# hbridge_ustx.net
KiCad netlist of a schematic drawn in EAGLE
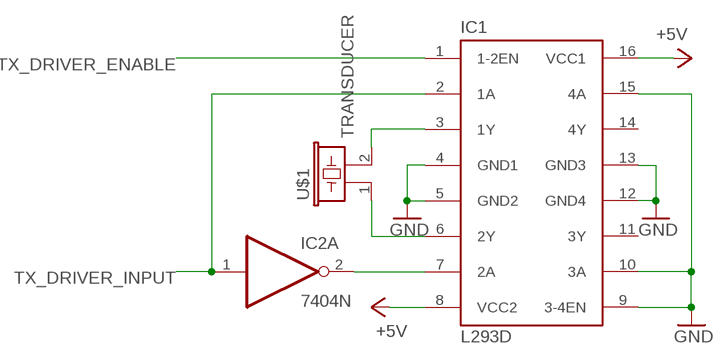
[diagram p0: schematic, sheet 1]

(export (version "E")
  (design (tool "Eeschema 10.0.6"))
  (components
    (comp (ref "IC1")
      (value "L293D")
      (footprint "eagle-import:DIL16")
      (libsource (lib "eagle-import") (part "L293D"))
    )
    (comp (ref "IC2")
      (value "7404N")
      (footprint "eagle-import:DIL14")
      (libsource (lib "eagle-import") (part "7404N"))
    )
    (comp (ref "U$1")
      (value "TRANSDUCER")
      (footprint "eagle-import:TRANSDUCER")
      (libsource (lib "eagle-import") (part "TRANSDUCER"))
    )
  )
  (nets
    (net (code "1") (name "+5V") (class "Default")
      (node (ref "IC1") (pin "16") (pinfunction "VCC1_16") (pintype "power_in"))
      (node (ref "IC1") (pin "8") (pinfunction "VCC2_8") (pintype "power_in"))
    )
    (net (code "2") (name "/TX_DRIVER_ENABLE") (class "Default")
      (node (ref "IC1") (pin "1") (pinfunction "1-2EN_1") (pintype "input"))
    )
    (net (code "3") (name "/TX_DRIVER_INPUT") (class "Default")
      (node (ref "IC1") (pin "2") (pinfunction "1A_2") (pintype "input"))
      (node (ref "IC2") (pin "1") (pinfunction "I_1") (pintype "input"))
    )
    (net (code "4") (name "GND") (class "Default")
      (node (ref "IC1") (pin "10") (pinfunction "3A_10") (pintype "input"))
      (node (ref "IC1") (pin "12") (pinfunction "GND4_12") (pintype "power_in"))
      (node (ref "IC1") (pin "13") (pinfunction "GND3_13") (pintype "power_in"))
      (node (ref "IC1") (pin "15") (pinfunction "4A_15") (pintype "input"))
      (node (ref "IC1") (pin "4") (pinfunction "GND1_4") (pintype "power_in"))
      (node (ref "IC1") (pin "5") (pinfunction "GND2_5") (pintype "power_in"))
      (node (ref "IC1") (pin "9") (pinfunction "3-4EN_9") (pintype "input"))
    )
    (net (code "5") (name "Net-(IC1-1Y)") (class "Default")
      (node (ref "IC1") (pin "3") (pinfunction "1Y_3") (pintype "output"))
      (node (ref "U$1") (pin "2") (pinfunction "2_2") (pintype "passive"))
    )
    (net (code "6") (name "Net-(IC1-2A)") (class "Default")
      (node (ref "IC1") (pin "7") (pinfunction "2A_7") (pintype "input"))
      (node (ref "IC2") (pin "2") (pinfunction "O_2") (pintype "output"))
    )
    (net (code "7") (name "Net-(IC1-2Y)") (class "Default")
      (node (ref "IC1") (pin "6") (pinfunction "2Y_6") (pintype "output"))
      (node (ref "U$1") (pin "1") (pinfunction "1_1") (pintype "passive"))
    )
    (net (code "8") (name "unconnected-(IC1-3Y-Pad11)") (class "Default")
      (node (ref "IC1") (pin "11") (pinfunction "3Y_11") (pintype "output"))
    )
    (net (code "9") (name "unconnected-(IC1-4Y-Pad14)") (class "Default")
      (node (ref "IC1") (pin "14") (pinfunction "4Y_14") (pintype "output"))
    )
  )
)
